# Sheet2.net
KiCad netlist of a schematic drawn in Altium Designer
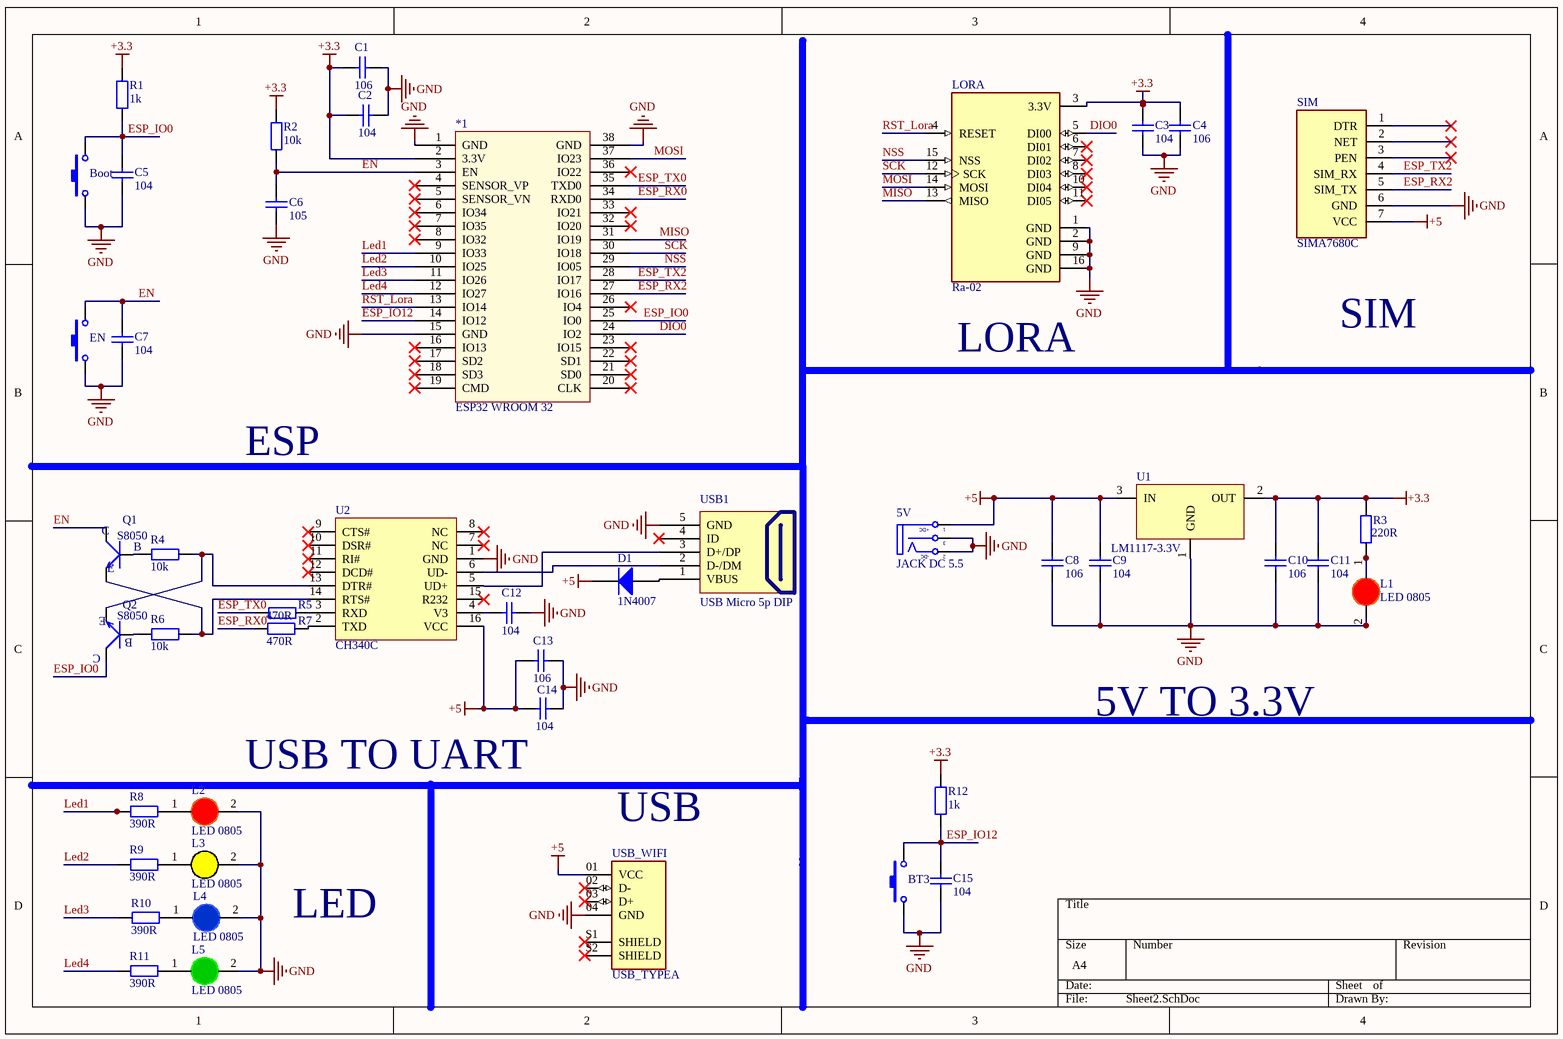
[diagram p0: Sheet2.SchDoc]

(export (version "E")
  (design (tool "Eeschema 10.0.6"))
  (components
    (comp (ref "*1")
      (value "ESP32 WROOM 32")
      (footprint "ESP32-WROOM-32D")
      (libsource (lib "Altium_Lib_by_KhueNguyenCreator") (part "ESP32 WROOM 32"))
    )
    (comp (ref "5V")
      (value "JACK DC 5.5")
      (footprint "JACK DC 5.5")
      (libsource (lib "Altium_Lib_by_KhueNguyenCreator") (part "JACK DC 5.5"))
    )
    (comp (ref "Boot")
      (value "Nut Nhan 2 Chan SMD 3x6x2.5")
      (footprint "Nut Nhan 2 Chan SMD 3x6x2.5")
      (libsource (lib "Altium_Lib_by_KhueNguyenCreator") (part "Nut Nhan 2 Chan SMD 3x6x2.5"))
    )
    (comp (ref "BT3")
      (value "Nut Nhan 2 Chan SMD 3x6x2.5")
      (footprint "Nut Nhan 2 Chan SMD 3x6x2.5")
      (libsource (lib "Altium_Lib_by_KhueNguyenCreator") (part "Nut Nhan 2 Chan SMD 3x6x2.5"))
    )
    (comp (ref "C1")
      (value "106")
      (footprint "tu 1206")
      (description "Dán")
      (libsource (lib "Altium_Lib_by_KhueNguyenCreator") (part "Tu 1206 106 16V 20%"))
    )
    (comp (ref "C2")
      (value "104")
      (footprint "tu 1206")
      (description "Dán")
      (libsource (lib "Altium_Lib_by_KhueNguyenCreator") (part "Tu 1206 104 50V 20%"))
    )
    (comp (ref "C3")
      (value "104")
      (footprint "tu 1206")
      (description "Dán")
      (libsource (lib "Altium_Lib_by_KhueNguyenCreator") (part "Tu 1206 104 50V 20%"))
    )
    (comp (ref "C4")
      (value "106")
      (footprint "tu 1206")
      (description "Dán")
      (libsource (lib "Altium_Lib_by_KhueNguyenCreator") (part "Tu 1206 106 16V 20%"))
    )
    (comp (ref "C5")
      (value "104")
      (footprint "tu 1206")
      (description "Dán")
      (libsource (lib "Altium_Lib_by_KhueNguyenCreator") (part "Tu 1206 104 50V 20%"))
    )
    (comp (ref "C6")
      (value "105")
      (footprint "tu 1206")
      (description "Dán")
      (libsource (lib "Altium_Lib_by_KhueNguyenCreator") (part "Tu 1206 105 50V 20%"))
    )
    (comp (ref "C7")
      (value "104")
      (footprint "tu 1206")
      (description "Dán")
      (libsource (lib "Altium_Lib_by_KhueNguyenCreator") (part "Tu 1206 104 50V 20%"))
    )
    (comp (ref "C8")
      (value "106")
      (footprint "tu 1206")
      (description "Dán")
      (libsource (lib "Altium_Lib_by_KhueNguyenCreator") (part "Tu 1206 106 16V 20%"))
    )
    (comp (ref "C9")
      (value "104")
      (footprint "tu 1206")
      (description "Dán")
      (libsource (lib "Altium_Lib_by_KhueNguyenCreator") (part "Tu 1206 104 50V 20%"))
    )
    (comp (ref "C10")
      (value "106")
      (footprint "tu 1206")
      (description "Dán")
      (libsource (lib "Altium_Lib_by_KhueNguyenCreator") (part "Tu 1206 106 16V 20%"))
    )
    (comp (ref "C11")
      (value "104")
      (footprint "tu 1206")
      (description "Dán")
      (libsource (lib "Altium_Lib_by_KhueNguyenCreator") (part "Tu 1206 104 50V 20%"))
    )
    (comp (ref "C12")
      (value "104")
      (footprint "tu 1206")
      (description "Dán")
      (libsource (lib "Altium_Lib_by_KhueNguyenCreator") (part "Tu 1206 104 50V 20%"))
    )
    (comp (ref "C13")
      (value "106")
      (footprint "tu 1206")
      (description "Dán")
      (libsource (lib "Altium_Lib_by_KhueNguyenCreator") (part "Tu 1206 106 16V 20%"))
    )
    (comp (ref "C14")
      (value "104")
      (footprint "tu 1206")
      (description "Dán")
      (libsource (lib "Altium_Lib_by_KhueNguyenCreator") (part "Tu 1206 104 50V 20%"))
    )
    (comp (ref "C15")
      (value "104")
      (footprint "tu 1206")
      (description "Dán")
      (libsource (lib "Altium_Lib_by_KhueNguyenCreator") (part "Tu 1206 104 50V 20%"))
    )
    (comp (ref "D1")
      (value "1N4007")
      (footprint "DIODE SMA")
      (description "Dán")
      (libsource (lib "Altium_Lib_by_KhueNguyenCreator") (part "Diode M7 ( 4007 )"))
    )
    (comp (ref "EN")
      (value "Nut Nhan 2 Chan SMD 3x6x2.5")
      (footprint "Nut Nhan 2 Chan SMD 3x6x2.5")
      (libsource (lib "Altium_Lib_by_KhueNguyenCreator") (part "Nut Nhan 2 Chan SMD 3x6x2.5"))
    )
    (comp (ref "L1")
      (value "LED 0805")
      (footprint "LED-1206-Red")
      (description "Dán")
      (libsource (lib "Altium_Lib_by_KhueNguyenCreator") (part "LED 1206 Do"))
    )
    (comp (ref "L2")
      (value "LED 0805")
      (footprint "LED-1206-Red")
      (description "Dán")
      (libsource (lib "Altium_Lib_by_KhueNguyenCreator") (part "LED 1206 Do"))
    )
    (comp (ref "L3")
      (value "LED 0805")
      (footprint "LED-1206-Yellow")
      (description "Dán")
      (libsource (lib "Altium_Lib_by_KhueNguyenCreator") (part "LED 1206 Vang"))
    )
    (comp (ref "L4")
      (value "LED 0805")
      (footprint "LED-1206-Blue")
      (description "Dán")
      (libsource (lib "Altium_Lib_by_KhueNguyenCreator") (part "LED 1206 Xanh Duong"))
    )
    (comp (ref "L5")
      (value "LED 0805")
      (footprint "LED-1206-Green")
      (description "Dán")
      (libsource (lib "Altium_Lib_by_KhueNguyenCreator") (part "LED 1206 Xanh La"))
    )
    (comp (ref "LORA")
      (value "Ra-02")
      (footprint "Sx1278")
      (description "Lora sx1278")
      (libsource (lib "My_lib") (part "Ra-02"))
    )
    (comp (ref "Q1")
      (value "S8050")
      (footprint "S8050")
      (description "Transistor NPN")
      (libsource (lib "My_lib") (part "S8050"))
    )
    (comp (ref "Q2")
      (value "S8050")
      (footprint "S8050")
      (description "Transistor NPN")
      (libsource (lib "My_lib") (part "S8050"))
    )
    (comp (ref "R1")
      (value "1k")
      (footprint "tro smd 1206")
      (description "Dán")
      (libsource (lib "Altium_Lib_by_KhueNguyenCreator") (part "Tro 1206 5% 1k"))
    )
    (comp (ref "R2")
      (value "10k")
      (footprint "tro smd 1206")
      (description "Dán")
      (libsource (lib "Altium_Lib_by_KhueNguyenCreator") (part "Tro 1206 1% 10k"))
    )
    (comp (ref "R3")
      (value "220R")
      (footprint "tro smd 1206")
      (description "Dán")
      (libsource (lib "Altium_Lib_by_KhueNguyenCreator") (part "Tro 1206 1% 220R"))
    )
    (comp (ref "R4")
      (value "10k")
      (footprint "tro smd 1206")
      (description "Dán")
      (libsource (lib "Altium_Lib_by_KhueNguyenCreator") (part "Tro 1206 5% 10k"))
    )
    (comp (ref "R5")
      (value "470R")
      (footprint "tro smd 1206")
      (description "Dán")
      (libsource (lib "Altium_Lib_by_KhueNguyenCreator") (part "Tro 1206 1% 680R"))
    )
    (comp (ref "R6")
      (value "10k")
      (footprint "tro smd 1206")
      (description "Dán")
      (libsource (lib "Altium_Lib_by_KhueNguyenCreator") (part "Tro 1206 5% 10k"))
    )
    (comp (ref "R7")
      (value "470R")
      (footprint "tro smd 1206")
      (description "Dán")
      (libsource (lib "Altium_Lib_by_KhueNguyenCreator") (part "Tro 1206 1% 680R"))
    )
    (comp (ref "R8")
      (value "390R")
      (footprint "Tro smd 1206")
      (description "Dán")
      (libsource (lib "Altium_Lib_by_KhueNguyenCreator") (part "Tro 1206 5% 390R"))
    )
    (comp (ref "R9")
      (value "390R")
      (footprint "Tro smd 1206")
      (description "Dán")
      (libsource (lib "Altium_Lib_by_KhueNguyenCreator") (part "Tro 1206 5% 390R"))
    )
    (comp (ref "R10")
      (value "390R")
      (footprint "Tro smd 1206")
      (description "Dán")
      (libsource (lib "Altium_Lib_by_KhueNguyenCreator") (part "Tro 1206 5% 390R"))
    )
    (comp (ref "R11")
      (value "390R")
      (footprint "Tro smd 1206")
      (description "Dán")
      (libsource (lib "Altium_Lib_by_KhueNguyenCreator") (part "Tro 1206 5% 390R"))
    )
    (comp (ref "R12")
      (value "1k")
      (footprint "tro smd 1206")
      (description "Dán")
      (libsource (lib "Altium_Lib_by_KhueNguyenCreator") (part "Tro 1206 5% 1k"))
    )
    (comp (ref "SIM")
      (value "SIMA7680C")
      (footprint "SIMA7680C")
      (libsource (lib "My_lib") (part "SIMA7680C"))
    )
    (comp (ref "U1")
      (value "LM1117-3.3V")
      (footprint "SOT223")
      (description "800mA Low-Dropout Linear Regulator")
      (fields (field (name "CREATOR") "Nguyen Ba Bien"))
      (libsource (lib "TechMT.VN_Lib_Project v2") (part "LM1117"))
    )
    (comp (ref "U2")
      (value "CH340C")
      (footprint "SOIC16_50_284_25X90_SMT")
      (description "USB Bridge, USB to UART USB 2.0 UART Interface")
      (fields (field (name "MANUFACTURER") "Olimex"))
      (libsource (lib "Altium_Lib_by_KhueNguyenCreator") (part "CH340C"))
    )
    (comp (ref "USB1")
      (value "USB Micro 5p DIP")
      (footprint "USB Micro 5p DIP")
      (description "USB Type B")
      (libsource (lib "Altium_Lib_by_KhueNguyenCreator") (part "USB Micro 5p DIP"))
    )
    (comp (ref "USB_WIFI")
      (value "USB_TYPEA")
      (footprint "USB_TYPEA")
      (libsource (lib "My_lib") (part "USB_TYPEA"))
    )
  )
  (nets
    (net (code "1") (name "+3.3") (class "Default")
      (node (ref "*1") (pin "2") (pinfunction "3.3V_2") (pintype "passive"))
      (node (ref "C1") (pin "2") (pinfunction "2_2") (pintype "passive"))
      (node (ref "C10") (pin "1") (pinfunction "1_1") (pintype "passive"))
      (node (ref "C11") (pin "1") (pinfunction "1_1") (pintype "passive"))
      (node (ref "C2") (pin "2") (pinfunction "2_2") (pintype "passive"))
      (node (ref "C3") (pin "1") (pinfunction "1_1") (pintype "passive"))
      (node (ref "C4") (pin "1") (pinfunction "1_1") (pintype "passive"))
      (node (ref "LORA") (pin "3") (pinfunction "3.3V_3") (pintype "power_in"))
      (node (ref "R1") (pin "2") (pinfunction "2_2") (pintype "passive"))
      (node (ref "R12") (pin "2") (pinfunction "2_2") (pintype "passive"))
      (node (ref "R2") (pin "2") (pinfunction "2_2") (pintype "passive"))
      (node (ref "R3") (pin "2") (pinfunction "2_2") (pintype "passive"))
      (node (ref "U1") (pin "2") (pinfunction "OUT_2") (pintype "passive"))
    )
    (net (code "2") (name "+5") (class "Default")
      (node (ref "5V") (pin "1") (pinfunction "T_1") (pintype "passive"))
      (node (ref "C13") (pin "1") (pinfunction "1_1") (pintype "passive"))
      (node (ref "C14") (pin "1") (pinfunction "1_1") (pintype "passive"))
      (node (ref "C8") (pin "1") (pinfunction "1_1") (pintype "passive"))
      (node (ref "C9") (pin "1") (pinfunction "1_1") (pintype "passive"))
      (node (ref "D1") (pin "2") (pinfunction "K_2") (pintype "passive"))
      (node (ref "SIM") (pin "7") (pinfunction "VCC_7") (pintype "power_in"))
      (node (ref "U1") (pin "3") (pinfunction "IN_3") (pintype "passive"))
      (node (ref "U2") (pin "16") (pinfunction "VCC_16") (pintype "passive"))
      (node (ref "USB_WIFI") (pin "01") (pinfunction "VCC_01") (pintype "power_in"))
    )
    (net (code "3") (name "/DIO0") (class "Default")
      (node (ref "*1") (pin "24") (pinfunction "IO2_24") (pintype "passive"))
      (node (ref "LORA") (pin "5") (pinfunction "DI00_5") (pintype "bidirectional"))
    )
    (net (code "4") (name "/EN") (class "Default")
      (node (ref "*1") (pin "3") (pinfunction "EN_3") (pintype "passive"))
      (node (ref "C6") (pin "1") (pinfunction "1_1") (pintype "passive"))
      (node (ref "C7") (pin "1") (pinfunction "1_1") (pintype "passive"))
      (node (ref "EN") (pin "2") (pinfunction "2_2") (pintype "passive"))
      (node (ref "Q1") (pin "3") (pinfunction "C_3") (pintype "passive"))
      (node (ref "R2") (pin "1") (pinfunction "1_1") (pintype "passive"))
    )
    (net (code "5") (name "/ESP_IO0") (class "Default")
      (node (ref "*1") (pin "25") (pinfunction "IO0_25") (pintype "passive"))
      (node (ref "Boot") (pin "2") (pinfunction "2_2") (pintype "passive"))
      (node (ref "C5") (pin "1") (pinfunction "1_1") (pintype "passive"))
      (node (ref "Q2") (pin "3") (pinfunction "C_3") (pintype "passive"))
      (node (ref "R1") (pin "1") (pinfunction "1_1") (pintype "passive"))
    )
    (net (code "6") (name "/ESP_IO12") (class "Default")
      (node (ref "*1") (pin "14") (pinfunction "IO12_14") (pintype "passive"))
      (node (ref "BT3") (pin "2") (pinfunction "2_2") (pintype "passive"))
      (node (ref "C15") (pin "1") (pinfunction "1_1") (pintype "passive"))
      (node (ref "R12") (pin "1") (pinfunction "1_1") (pintype "passive"))
    )
    (net (code "7") (name "/ESP_RX0") (class "Default")
      (node (ref "*1") (pin "34") (pinfunction "RXD0_34") (pintype "passive"))
      (node (ref "R7") (pin "1") (pinfunction "1_1") (pintype "passive"))
    )
    (net (code "8") (name "/ESP_RX2") (class "Default")
      (node (ref "*1") (pin "27") (pinfunction "IO16_27") (pintype "passive"))
      (node (ref "SIM") (pin "5") (pinfunction "SIM_TX_5") (pintype "power_in"))
    )
    (net (code "9") (name "/ESP_TX0") (class "Default")
      (node (ref "*1") (pin "35") (pinfunction "TXD0_35") (pintype "passive"))
      (node (ref "R5") (pin "1") (pinfunction "1_1") (pintype "passive"))
    )
    (net (code "10") (name "/ESP_TX2") (class "Default")
      (node (ref "*1") (pin "28") (pinfunction "IO17_28") (pintype "passive"))
      (node (ref "SIM") (pin "4") (pinfunction "SIM_RX_4") (pintype "power_in"))
    )
    (net (code "11") (name "/Led1") (class "Default")
      (node (ref "*1") (pin "9") (pinfunction "IO33_9") (pintype "passive"))
      (node (ref "R8") (pin "2") (pinfunction "2_2") (pintype "passive"))
    )
    (net (code "12") (name "/Led2") (class "Default")
      (node (ref "*1") (pin "10") (pinfunction "IO25_10") (pintype "passive"))
      (node (ref "R9") (pin "2") (pinfunction "2_2") (pintype "passive"))
    )
    (net (code "13") (name "/Led3") (class "Default")
      (node (ref "*1") (pin "11") (pinfunction "IO26_11") (pintype "passive"))
      (node (ref "R10") (pin "2") (pinfunction "2_2") (pintype "passive"))
    )
    (net (code "14") (name "/Led4") (class "Default")
      (node (ref "*1") (pin "12") (pinfunction "IO27_12") (pintype "passive"))
      (node (ref "R11") (pin "2") (pinfunction "2_2") (pintype "passive"))
    )
    (net (code "15") (name "/MISO") (class "Default")
      (node (ref "*1") (pin "31") (pinfunction "IO19_31") (pintype "passive"))
      (node (ref "LORA") (pin "13") (pinfunction "MISO_13") (pintype "output"))
    )
    (net (code "16") (name "/MOSI") (class "Default")
      (node (ref "*1") (pin "37") (pinfunction "IO23_37") (pintype "passive"))
      (node (ref "LORA") (pin "14") (pinfunction "MOSI_14") (pintype "input"))
    )
    (net (code "17") (name "/NSS") (class "Default")
      (node (ref "*1") (pin "29") (pinfunction "IO05_29") (pintype "passive"))
      (node (ref "LORA") (pin "15") (pinfunction "NSS_15") (pintype "input"))
    )
    (net (code "18") (name "/RST_Lora") (class "Default")
      (node (ref "*1") (pin "13") (pinfunction "IO14_13") (pintype "passive"))
      (node (ref "LORA") (pin "4") (pinfunction "RESET_4") (pintype "input"))
    )
    (net (code "19") (name "/SCK") (class "Default")
      (node (ref "*1") (pin "30") (pinfunction "IO18_30") (pintype "passive"))
      (node (ref "LORA") (pin "12") (pinfunction "SCK_12") (pintype "input"))
    )
    (net (code "20") (name "GND") (class "Default")
      (node (ref "*1") (pin "1") (pinfunction "GND_1") (pintype "passive"))
      (node (ref "*1") (pin "15") (pinfunction "GND_15") (pintype "passive"))
      (node (ref "*1") (pin "38") (pinfunction "GND_38") (pintype "passive"))
      (node (ref "5V") (pin "2") (pinfunction "TN_2") (pintype "passive"))
      (node (ref "5V") (pin "3") (pinfunction "S_3") (pintype "power_in"))
      (node (ref "BT3") (pin "1") (pinfunction "1_1") (pintype "passive"))
      (node (ref "Boot") (pin "1") (pinfunction "1_1") (pintype "passive"))
      (node (ref "C1") (pin "1") (pinfunction "1_1") (pintype "passive"))
      (node (ref "C10") (pin "2") (pinfunction "2_2") (pintype "passive"))
      (node (ref "C11") (pin "2") (pinfunction "2_2") (pintype "passive"))
      (node (ref "C12") (pin "2") (pinfunction "2_2") (pintype "passive"))
      (node (ref "C13") (pin "2") (pinfunction "2_2") (pintype "passive"))
      (node (ref "C14") (pin "2") (pinfunction "2_2") (pintype "passive"))
      (node (ref "C15") (pin "2") (pinfunction "2_2") (pintype "passive"))
      (node (ref "C2") (pin "1") (pinfunction "1_1") (pintype "passive"))
      (node (ref "C3") (pin "2") (pinfunction "2_2") (pintype "passive"))
      (node (ref "C4") (pin "2") (pinfunction "2_2") (pintype "passive"))
      (node (ref "C5") (pin "2") (pinfunction "2_2") (pintype "passive"))
      (node (ref "C6") (pin "2") (pinfunction "2_2") (pintype "passive"))
      (node (ref "C7") (pin "2") (pinfunction "2_2") (pintype "passive"))
      (node (ref "C8") (pin "2") (pinfunction "2_2") (pintype "passive"))
      (node (ref "C9") (pin "2") (pinfunction "2_2") (pintype "passive"))
      (node (ref "EN") (pin "1") (pinfunction "1_1") (pintype "passive"))
      (node (ref "L1") (pin "2") (pinfunction "K_2") (pintype "passive"))
      (node (ref "L2") (pin "2") (pinfunction "K_2") (pintype "passive"))
      (node (ref "L3") (pin "2") (pinfunction "K_2") (pintype "passive"))
      (node (ref "L4") (pin "2") (pinfunction "K_2") (pintype "passive"))
      (node (ref "L5") (pin "2") (pinfunction "K_2") (pintype "passive"))
      (node (ref "LORA") (pin "1") (pinfunction "GND_1") (pintype "power_in"))
      (node (ref "LORA") (pin "16") (pinfunction "GND_16") (pintype "power_in"))
      (node (ref "LORA") (pin "2") (pinfunction "GND_2") (pintype "power_in"))
      (node (ref "LORA") (pin "9") (pinfunction "GND_9") (pintype "power_in"))
      (node (ref "SIM") (pin "6") (pinfunction "GND_6") (pintype "power_in"))
      (node (ref "U1") (pin "1") (pinfunction "GND_1") (pintype "passive"))
      (node (ref "U2") (pin "1") (pinfunction "GND_1") (pintype "passive"))
      (node (ref "USB1") (pin "5") (pinfunction "GND_5") (pintype "passive"))
      (node (ref "USB_WIFI") (pin "04") (pinfunction "GND_04") (pintype "power_in"))
    )
    (net (code "21") (name "Net-(D1-A)") (class "Default")
      (node (ref "D1") (pin "1") (pinfunction "A_1") (pintype "passive"))
      (node (ref "USB1") (pin "1") (pinfunction "VBUS_1") (pintype "passive"))
    )
    (net (code "22") (name "Net-(L1-A)") (class "Default")
      (node (ref "L1") (pin "1") (pinfunction "A_1") (pintype "passive"))
      (node (ref "R3") (pin "1") (pinfunction "1_1") (pintype "passive"))
    )
    (net (code "23") (name "Net-(L2-A)") (class "Default")
      (node (ref "L2") (pin "1") (pinfunction "A_1") (pintype "passive"))
      (node (ref "R8") (pin "1") (pinfunction "1_1") (pintype "passive"))
    )
    (net (code "24") (name "Net-(L3-A)") (class "Default")
      (node (ref "L3") (pin "1") (pinfunction "A_1") (pintype "passive"))
      (node (ref "R9") (pin "1") (pinfunction "1_1") (pintype "passive"))
    )
    (net (code "25") (name "Net-(L4-A)") (class "Default")
      (node (ref "L4") (pin "1") (pinfunction "A_1") (pintype "passive"))
      (node (ref "R10") (pin "1") (pinfunction "1_1") (pintype "passive"))
    )
    (net (code "26") (name "Net-(L5-A)") (class "Default")
      (node (ref "L5") (pin "1") (pinfunction "A_1") (pintype "passive"))
      (node (ref "R11") (pin "1") (pinfunction "1_1") (pintype "passive"))
    )
    (net (code "27") (name "Net-(Q1-B)") (class "Default")
      (node (ref "Q1") (pin "1") (pinfunction "B_1") (pintype "passive"))
      (node (ref "R4") (pin "1") (pinfunction "1_1") (pintype "passive"))
    )
    (net (code "28") (name "Net-(Q1-E)") (class "Default")
      (node (ref "Q1") (pin "2") (pinfunction "E_2") (pintype "passive"))
      (node (ref "R6") (pin "2") (pinfunction "2_2") (pintype "passive"))
      (node (ref "U2") (pin "14") (pinfunction "RTS#_14") (pintype "passive"))
    )
    (net (code "29") (name "Net-(Q2-B)") (class "Default")
      (node (ref "Q2") (pin "1") (pinfunction "B_1") (pintype "passive"))
      (node (ref "R6") (pin "1") (pinfunction "1_1") (pintype "passive"))
    )
    (net (code "30") (name "Net-(Q2-E)") (class "Default")
      (node (ref "Q2") (pin "2") (pinfunction "E_2") (pintype "passive"))
      (node (ref "R4") (pin "2") (pinfunction "2_2") (pintype "passive"))
      (node (ref "U2") (pin "13") (pinfunction "DTR#_13") (pintype "passive"))
    )
    (net (code "31") (name "Net-(U2-RXD)") (class "Default")
      (node (ref "R5") (pin "2") (pinfunction "2_2") (pintype "passive"))
      (node (ref "U2") (pin "3") (pinfunction "RXD_3") (pintype "passive"))
    )
    (net (code "32") (name "Net-(U2-TXD)") (class "Default")
      (node (ref "R7") (pin "2") (pinfunction "2_2") (pintype "passive"))
      (node (ref "U2") (pin "2") (pinfunction "TXD_2") (pintype "passive"))
    )
    (net (code "33") (name "Net-(U2-UD+)") (class "Default")
      (node (ref "U2") (pin "5") (pinfunction "UD+_5") (pintype "passive"))
      (node (ref "USB1") (pin "3") (pinfunction "D+/DP_3") (pintype "passive"))
    )
    (net (code "34") (name "Net-(U2-UD-)") (class "Default")
      (node (ref "U2") (pin "6") (pinfunction "UD-_6") (pintype "passive"))
      (node (ref "USB1") (pin "2") (pinfunction "D-/DM_2") (pintype "passive"))
    )
    (net (code "35") (name "Net-(U2-V3)") (class "Default")
      (node (ref "C12") (pin "1") (pinfunction "1_1") (pintype "passive"))
      (node (ref "U2") (pin "4") (pinfunction "V3_4") (pintype "passive"))
    )
    (net (code "36") (name "unconnected-(*1-CLK-Pad20)") (class "Default")
      (node (ref "*1") (pin "20") (pinfunction "CLK_20") (pintype "passive+no_connect"))
    )
    (net (code "37") (name "unconnected-(*1-CMD-Pad19)") (class "Default")
      (node (ref "*1") (pin "19") (pinfunction "CMD_19") (pintype "passive+no_connect"))
    )
    (net (code "38") (name "unconnected-(*1-IO4-Pad26)") (class "Default")
      (node (ref "*1") (pin "26") (pinfunction "IO4_26") (pintype "passive+no_connect"))
    )
    (net (code "39") (name "unconnected-(*1-IO13-Pad16)") (class "Default")
      (node (ref "*1") (pin "16") (pinfunction "IO13_16") (pintype "passive+no_connect"))
    )
    (net (code "40") (name "unconnected-(*1-IO15-Pad23)") (class "Default")
      (node (ref "*1") (pin "23") (pinfunction "IO15_23") (pintype "passive+no_connect"))
    )
    (net (code "41") (name "unconnected-(*1-IO20-Pad32)") (class "Default")
      (node (ref "*1") (pin "32") (pinfunction "IO20_32") (pintype "passive+no_connect"))
    )
    (net (code "42") (name "unconnected-(*1-IO21-Pad33)") (class "Default")
      (node (ref "*1") (pin "33") (pinfunction "IO21_33") (pintype "passive+no_connect"))
    )
    (net (code "43") (name "unconnected-(*1-IO22-Pad36)") (class "Default")
      (node (ref "*1") (pin "36") (pinfunction "IO22_36") (pintype "passive+no_connect"))
    )
    (net (code "44") (name "unconnected-(*1-IO32-Pad8)") (class "Default")
      (node (ref "*1") (pin "8") (pinfunction "IO32_8") (pintype "passive+no_connect"))
    )
    (net (code "45") (name "unconnected-(*1-IO34-Pad6)") (class "Default")
      (node (ref "*1") (pin "6") (pinfunction "IO34_6") (pintype "passive+no_connect"))
    )
    (net (code "46") (name "unconnected-(*1-IO35-Pad7)") (class "Default")
      (node (ref "*1") (pin "7") (pinfunction "IO35_7") (pintype "passive+no_connect"))
    )
    (net (code "47") (name "unconnected-(*1-SD0-Pad21)") (class "Default")
      (node (ref "*1") (pin "21") (pinfunction "SD0_21") (pintype "passive+no_connect"))
    )
    (net (code "48") (name "unconnected-(*1-SD1-Pad22)") (class "Default")
      (node (ref "*1") (pin "22") (pinfunction "SD1_22") (pintype "passive+no_connect"))
    )
    (net (code "49") (name "unconnected-(*1-SD2-Pad17)") (class "Default")
      (node (ref "*1") (pin "17") (pinfunction "SD2_17") (pintype "passive+no_connect"))
    )
    (net (code "50") (name "unconnected-(*1-SD3-Pad18)") (class "Default")
      (node (ref "*1") (pin "18") (pinfunction "SD3_18") (pintype "passive+no_connect"))
    )
    (net (code "51") (name "unconnected-(*1-SENSOR_VN-Pad5)") (class "Default")
      (node (ref "*1") (pin "5") (pinfunction "SENSOR_VN_5") (pintype "passive+no_connect"))
    )
    (net (code "52") (name "unconnected-(*1-SENSOR_VP-Pad4)") (class "Default")
      (node (ref "*1") (pin "4") (pinfunction "SENSOR_VP_4") (pintype "passive+no_connect"))
    )
    (net (code "53") (name "unconnected-(LORA-DI01-Pad6)") (class "Default")
      (node (ref "LORA") (pin "6") (pinfunction "DI01_6") (pintype "bidirectional+no_connect"))
    )
    (net (code "54") (name "unconnected-(LORA-DI02-Pad7)") (class "Default")
      (node (ref "LORA") (pin "7") (pinfunction "DI02_7") (pintype "bidirectional+no_connect"))
    )
    (net (code "55") (name "unconnected-(LORA-DI03-Pad8)") (class "Default")
      (node (ref "LORA") (pin "8") (pinfunction "DI03_8") (pintype "bidirectional+no_connect"))
    )
    (net (code "56") (name "unconnected-(LORA-DI04-Pad10)") (class "Default")
      (node (ref "LORA") (pin "10") (pinfunction "DI04_10") (pintype "bidirectional+no_connect"))
    )
    (net (code "57") (name "unconnected-(LORA-DI05-Pad11)") (class "Default")
      (node (ref "LORA") (pin "11") (pinfunction "DI05_11") (pintype "bidirectional+no_connect"))
    )
    (net (code "58") (name "unconnected-(SIM-DTR-Pad1)") (class "Default")
      (node (ref "SIM") (pin "1") (pinfunction "DTR_1") (pintype "passive+no_connect"))
    )
    (net (code "59") (name "unconnected-(SIM-NET-Pad2)") (class "Default")
      (node (ref "SIM") (pin "2") (pinfunction "NET_2") (pintype "passive+no_connect"))
    )
    (net (code "60") (name "unconnected-(SIM-PEN-Pad3)") (class "Default")
      (node (ref "SIM") (pin "3") (pinfunction "PEN_3") (pintype "power_in+no_connect"))
    )
    (net (code "61") (name "unconnected-(U2-CTS#-Pad9)") (class "Default")
      (node (ref "U2") (pin "9") (pinfunction "CTS#_9") (pintype "passive+no_connect"))
    )
    (net (code "62") (name "unconnected-(U2-DCD#-Pad12)") (class "Default")
      (node (ref "U2") (pin "12") (pinfunction "DCD#_12") (pintype "passive+no_connect"))
    )
    (net (code "63") (name "unconnected-(U2-DSR#-Pad10)") (class "Default")
      (node (ref "U2") (pin "10") (pinfunction "DSR#_10") (pintype "passive+no_connect"))
    )
    (net (code "64") (name "unconnected-(U2-NC-Pad7)") (class "Default")
      (node (ref "U2") (pin "7") (pinfunction "NC_7") (pintype "passive+no_connect"))
    )
    (net (code "65") (name "unconnected-(U2-NC-Pad8)") (class "Default")
      (node (ref "U2") (pin "8") (pinfunction "NC_8") (pintype "passive+no_connect"))
    )
    (net (code "66") (name "unconnected-(U2-R232-Pad15)") (class "Default")
      (node (ref "U2") (pin "15") (pinfunction "R232_15") (pintype "passive+no_connect"))
    )
    (net (code "67") (name "unconnected-(U2-RI#-Pad11)") (class "Default")
      (node (ref "U2") (pin "11") (pinfunction "RI#_11") (pintype "passive+no_connect"))
    )
    (net (code "68") (name "unconnected-(USB1-ID-Pad4)") (class "Default")
      (node (ref "USB1") (pin "4") (pinfunction "ID_4") (pintype "passive+no_connect"))
    )
    (net (code "69") (name "unconnected-(USB_WIFI-D+-Pad03)") (class "Default")
      (node (ref "USB_WIFI") (pin "03") (pinfunction "D+_03") (pintype "bidirectional+no_connect"))
    )
    (net (code "70") (name "unconnected-(USB_WIFI-D--Pad02)") (class "Default")
      (node (ref "USB_WIFI") (pin "02") (pinfunction "D-_02") (pintype "bidirectional+no_connect"))
    )
    (net (code "71") (name "unconnected-(USB_WIFI-SHIELD-PadS1)") (class "Default")
      (node (ref "USB_WIFI") (pin "S1") (pinfunction "SHIELD_S1") (pintype "passive+no_connect"))
    )
    (net (code "72") (name "unconnected-(USB_WIFI-SHIELD-PadS2)") (class "Default")
      (node (ref "USB_WIFI") (pin "S2") (pinfunction "SHIELD_S2") (pintype "passive+no_connect"))
    )
  )
)
